# 11_RS232_2.net
KiCad netlist of a schematic drawn in Altium Designer
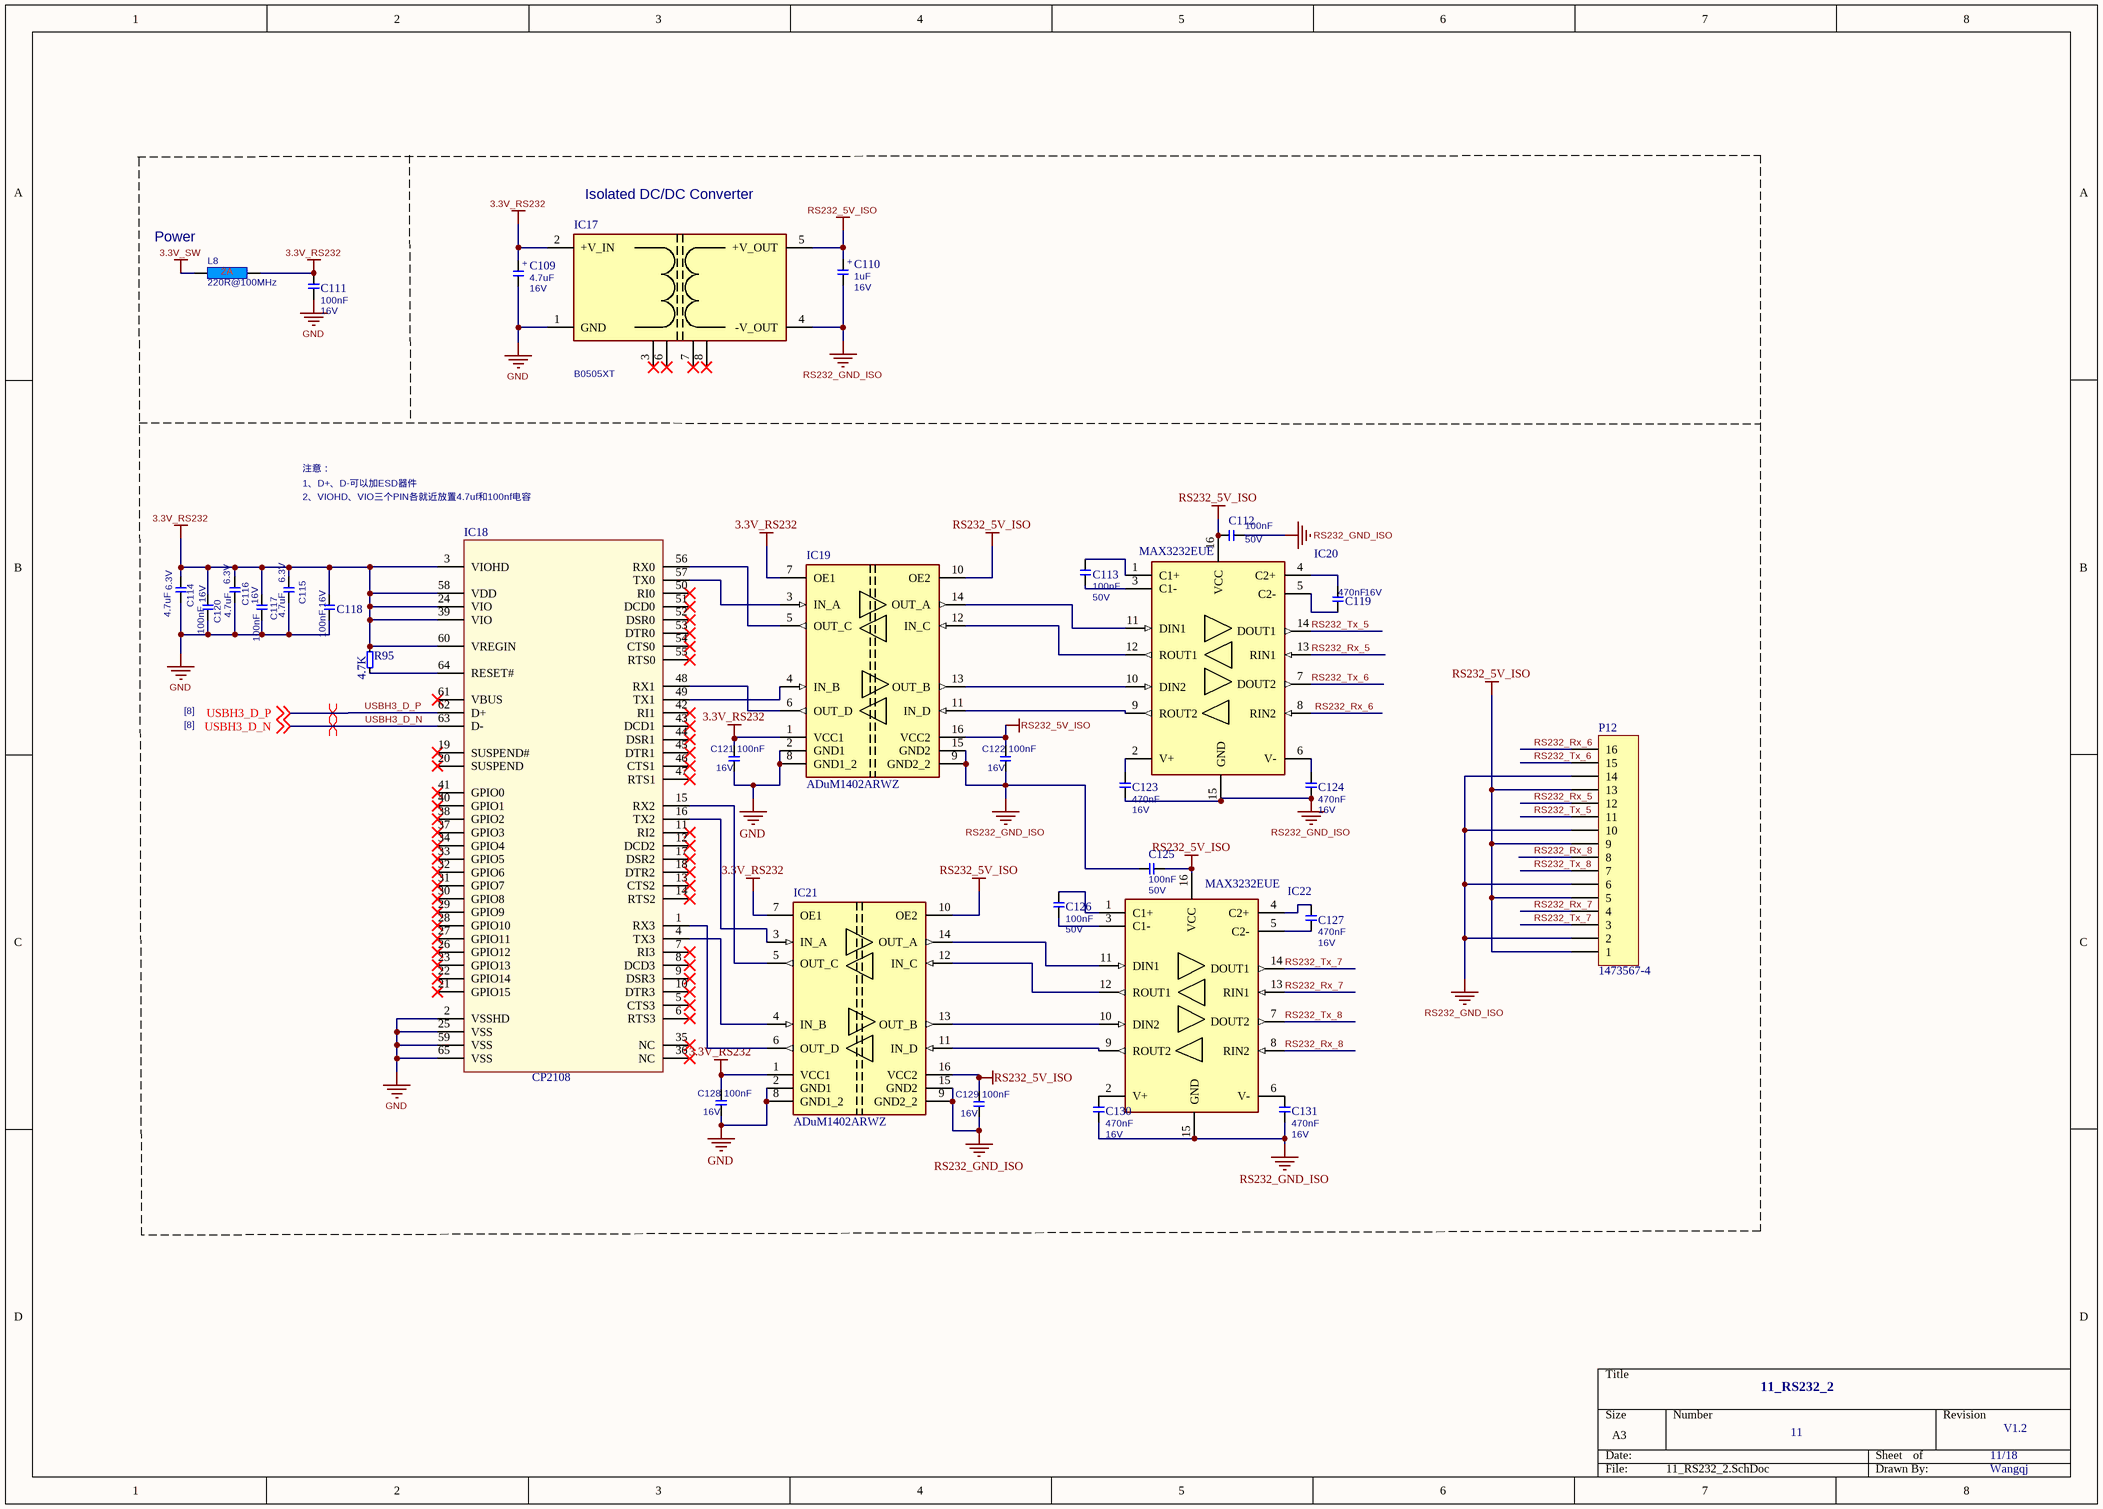
[diagram p0: 11_RS232_2.SchDoc]

(export (version "E")
  (design (tool "Eeschema 10.0.6"))
  (components
    (comp (ref "C109")
      (value "4.7uF")
      (footprint "T_CAPMP3216X180N")
      (description "Capacitor TA 4.7uF 16V 10% 3216")
      (fields (field (name "TOLERANCE") "10%") (field (name "RATING") "16V"))
      (libsource (lib "Apalis Evaluation Board") (part "C-4.7uF-16V-10%-3216-TA"))
    )
    (comp (ref "C110")
      (value "1uF")
      (footprint "T_CAPMP3216X180N")
      (description "Capacitor TA 1uF 16V 10% 3216")
      (fields (field (name "TOLERANCE") "10%") (field (name "RATING") "16V"))
      (libsource (lib "Apalis Evaluation Board") (part "C-1uF-16V-10%-3216-TA"))
    )
    (comp (ref "C111")
      (value "100nF")
      (footprint "T_CAPC0603X33N")
      (description "Capacitor Ceramic X7R 100nF 16V 10% 0603")
      (fields (field (name "TOLERANCE") "10%") (field (name "RATING") "16V"))
      (libsource (lib "Apalis Evaluation Board") (part "C-100nF-16V-10%-0603-X7R"))
    )
    (comp (ref "C112")
      (value "100nF")
      (footprint "T_CAPC0603X33N")
      (description "Capacitor Ceramic X7R 100nF 50V 20% 0603")
      (fields (field (name "TOLERANCE") "20%") (field (name "RATING") "50V"))
      (libsource (lib "Apalis Evaluation Board") (part "C-X7R-100nF-50V-20%-0603"))
    )
    (comp (ref "C113")
      (value "100nF")
      (footprint "T_CAPC0603X33N")
      (description "Capacitor Ceramic X7R 100nF 50V 20% 0603")
      (fields (field (name "TOLERANCE") "20%") (field (name "RATING") "50V"))
      (libsource (lib "Apalis Evaluation Board") (part "C-X7R-100nF-50V-20%-0603"))
    )
    (comp (ref "C114")
      (value "4.7uF")
      (footprint "T_CAPC0603X33N")
      (description "Capacitor Ceramic X5R 4.7uF 6.3V 20% 0603")
      (fields (field (name "TOLERANCE") "20%") (field (name "RATING") "6.3V"))
      (libsource (lib "Apalis Evaluation Board") (part "C-4.7uF-6.3V-20%-0603-X5R"))
    )
    (comp (ref "C115")
      (value "4.7uF")
      (footprint "T_CAPC0603X33N")
      (description "Capacitor Ceramic X5R 4.7uF 6.3V 20% 0603")
      (fields (field (name "TOLERANCE") "20%") (field (name "RATING") "6.3V"))
      (libsource (lib "Apalis Evaluation Board") (part "C-4.7uF-6.3V-20%-0603-X5R"))
    )
    (comp (ref "C116")
      (value "4.7uF")
      (footprint "T_CAPC0603X33N")
      (description "Capacitor Ceramic X5R 4.7uF 6.3V 20% 0603")
      (fields (field (name "TOLERANCE") "20%") (field (name "RATING") "6.3V"))
      (libsource (lib "Apalis Evaluation Board") (part "C-4.7uF-6.3V-20%-0603-X5R"))
    )
    (comp (ref "C117")
      (value "100nF")
      (footprint "T_CAPC0603X33N")
      (description "Capacitor Ceramic X7R 100nF 16V 10% 0603")
      (fields (field (name "TOLERANCE") "10%") (field (name "RATING") "16V"))
      (libsource (lib "Apalis Evaluation Board") (part "C-100nF-16V-10%-0603-X7R"))
    )
    (comp (ref "C118")
      (value "100nF")
      (footprint "T_CAPC0603X33N")
      (description "Capacitor Ceramic X7R 100nF 16V 10% 0603")
      (fields (field (name "TOLERANCE") "10%") (field (name "RATING") "16V"))
      (libsource (lib "Apalis Evaluation Board") (part "C-100nF-16V-10%-0603-X7R"))
    )
    (comp (ref "C119")
      (value "470nF")
      (footprint "T_CAPC0603X33N")
      (description "Capacitor Ceramic X7R 470nF 16V 10% 0603")
      (fields (field (name "TOLERANCE") "10%") (field (name "RATING") "16V"))
      (libsource (lib "Apalis Evaluation Board") (part "C-X7R-470nF-16V-10%-0603"))
    )
    (comp (ref "C120")
      (value "100nF")
      (footprint "T_CAPC0603X33N")
      (description "Capacitor Ceramic X7R 100nF 16V 10% 0603")
      (fields (field (name "TOLERANCE") "10%") (field (name "RATING") "16V"))
      (libsource (lib "Apalis Evaluation Board") (part "C-100nF-16V-10%-0603-X7R"))
    )
    (comp (ref "C121")
      (value "100nF")
      (footprint "T_CAPC0603X33N")
      (description "Capacitor Ceramic X7R 100nF 16V 10% 0603")
      (fields (field (name "TOLERANCE") "10%") (field (name "RATING") "16V"))
      (libsource (lib "Apalis Evaluation Board") (part "C-X7R-100nF-16V-10%-0603"))
    )
    (comp (ref "C122")
      (value "100nF")
      (footprint "T_CAPC0603X33N")
      (description "Capacitor Ceramic X7R 100nF 16V 10% 0603")
      (fields (field (name "TOLERANCE") "10%") (field (name "RATING") "16V"))
      (libsource (lib "Apalis Evaluation Board") (part "C-X7R-100nF-16V-10%-0603"))
    )
    (comp (ref "C123")
      (value "470nF")
      (footprint "T_CAPC0603X33N")
      (description "Capacitor Ceramic X7R 470nF 16V 10% 0603")
      (fields (field (name "TOLERANCE") "10%") (field (name "RATING") "16V"))
      (libsource (lib "Apalis Evaluation Board") (part "C-X7R-470nF-16V-10%-0603"))
    )
    (comp (ref "C124")
      (value "470nF")
      (footprint "T_CAPC0603X33N")
      (description "Capacitor Ceramic X7R 470nF 16V 10% 0603")
      (fields (field (name "TOLERANCE") "10%") (field (name "RATING") "16V"))
      (libsource (lib "Apalis Evaluation Board") (part "C-X7R-470nF-16V-10%-0603"))
    )
    (comp (ref "C125")
      (value "100nF")
      (footprint "T_CAPC0603X33N")
      (description "Capacitor Ceramic X7R 100nF 50V 20% 0603")
      (fields (field (name "TOLERANCE") "20%") (field (name "RATING") "50V"))
      (libsource (lib "Apalis Evaluation Board") (part "C-X7R-100nF-50V-20%-0603"))
    )
    (comp (ref "C126")
      (value "100nF")
      (footprint "T_CAPC0603X33N")
      (description "Capacitor Ceramic X7R 100nF 50V 20% 0603")
      (fields (field (name "TOLERANCE") "20%") (field (name "RATING") "50V"))
      (libsource (lib "Apalis Evaluation Board") (part "C-X7R-100nF-50V-20%-0603"))
    )
    (comp (ref "C127")
      (value "470nF")
      (footprint "T_CAPC0603X33N")
      (description "Capacitor Ceramic X7R 470nF 16V 10% 0603")
      (fields (field (name "TOLERANCE") "10%") (field (name "RATING") "16V"))
      (libsource (lib "Apalis Evaluation Board") (part "C-X7R-470nF-16V-10%-0603"))
    )
    (comp (ref "C128")
      (value "100nF")
      (footprint "T_CAPC0603X33N")
      (description "Capacitor Ceramic X7R 100nF 16V 10% 0603")
      (fields (field (name "TOLERANCE") "10%") (field (name "RATING") "16V"))
      (libsource (lib "Apalis Evaluation Board") (part "C-X7R-100nF-16V-10%-0603"))
    )
    (comp (ref "C129")
      (value "100nF")
      (footprint "T_CAPC0603X33N")
      (description "Capacitor Ceramic X7R 100nF 16V 10% 0603")
      (fields (field (name "TOLERANCE") "10%") (field (name "RATING") "16V"))
      (libsource (lib "Apalis Evaluation Board") (part "C-X7R-100nF-16V-10%-0603"))
    )
    (comp (ref "C130")
      (value "470nF")
      (footprint "T_CAPC0603X33N")
      (description "Capacitor Ceramic X7R 470nF 16V 10% 0603")
      (fields (field (name "TOLERANCE") "10%") (field (name "RATING") "16V"))
      (libsource (lib "Apalis Evaluation Board") (part "C-X7R-470nF-16V-10%-0603"))
    )
    (comp (ref "C131")
      (value "470nF")
      (footprint "T_CAPC0603X33N")
      (description "Capacitor Ceramic X7R 470nF 16V 10% 0603")
      (fields (field (name "TOLERANCE") "10%") (field (name "RATING") "16V"))
      (libsource (lib "Apalis Evaluation Board") (part "C-X7R-470nF-16V-10%-0603"))
    )
    (comp (ref "IC17")
      (value "B0505XT-1W")
      (footprint "MORNSUN_B0305XT-1W_SMD")
      (description "MORNSUN Isolated DC/DC Converter")
      (fields (field (name "MANUFACTURER PART NO.") "B0505XT"))
      (libsource (lib "Apalis Evaluation Board") (part "IC-MORNSUN-B0505XT-SMD"))
    )
    (comp (ref "IC18")
      (value "CP2108")
      (footprint "QFN50P900X900X90_HS-65N")
      (description "Single-Chip USB To Quad UART Bridge")
      (fields (field (name "MANUCFACTURER PART NO.") "CP2108"))
      (libsource (lib "Apalis Evaluation Board") (part "IC-SILICON-CP2108"))
    )
    (comp (ref "IC19")
      (value "ADuM1402ARWZ")
      (footprint "T_AD_ADuM1300ARW")
      (description "Digital Isolator")
      (libsource (lib "Apalis Evaluation Board") (part "IC-AD-ADuM1402ARWZ"))
    )
    (comp (ref "IC20")
      (value "MAX3232EUE")
      (footprint "LC-TSSOP-16")
      (description "RS232")
      (libsource (lib "Apalis Evaluation Board") (part "IC-MAXIM-MAX3232"))
    )
    (comp (ref "IC21")
      (value "ADuM1402ARWZ")
      (footprint "T_AD_ADuM1300ARW")
      (description "Digital Isolator")
      (libsource (lib "Apalis Evaluation Board") (part "IC-AD-ADuM1402ARWZ"))
    )
    (comp (ref "IC22")
      (value "MAX3232EUE")
      (footprint "LC-TSSOP-16")
      (description "RS232")
      (libsource (lib "Apalis Evaluation Board") (part "IC-MAXIM-MAX3232"))
    )
    (comp (ref "L8")
      (value "220R@100MHz")
      (footprint "INDC1608X95N")
      (description "220R@100MHz 2A EMI FILTER")
      (fields (field (name "TOLERANCE") "25%"))
      (libsource (lib "Apalis Evaluation Board") (part "L-220R@100MHz-2A-25%-0603"))
    )
    (comp (ref "P12")
      (value "1473567-4")
      (footprint "147-4")
      (description "泰科4P端子")
      (fields (field (name "PUBLISHER") "Altium Limited"))
      (libsource (lib "Miscellaneous Connectors") (part "MHDR1X16"))
    )
    (comp (ref "R95")
      (value "4.7K")
      (footprint "t_RESC0603X30N")
      (description "Resistor 4.7 Kohm 63mW 5% 0603")
      (fields (field (name "TOLERANCE") "5%"))
      (libsource (lib "Apalis Evaluation Board") (part "R-4.7kR-63mW-5%-0603"))
    )
  )
  (nets
    (net (code "1") (name "/RS232_Rx_5") (class "Default")
      (node (ref "IC20") (pin "13") (pinfunction "RIN1_13") (pintype "input"))
      (node (ref "P12") (pin "12") (pinfunction "12_12") (pintype "passive"))
    )
    (net (code "2") (name "/RS232_Rx_6") (class "Default")
      (node (ref "IC20") (pin "8") (pinfunction "RIN2_8") (pintype "input"))
      (node (ref "P12") (pin "16") (pinfunction "16_16") (pintype "passive"))
    )
    (net (code "3") (name "/RS232_Rx_7") (class "Default")
      (node (ref "IC22") (pin "13") (pinfunction "RIN1_13") (pintype "input"))
      (node (ref "P12") (pin "4") (pinfunction "4_4") (pintype "passive"))
    )
    (net (code "4") (name "/RS232_Rx_8") (class "Default")
      (node (ref "IC22") (pin "8") (pinfunction "RIN2_8") (pintype "input"))
      (node (ref "P12") (pin "8") (pinfunction "8_8") (pintype "passive"))
    )
    (net (code "5") (name "/RS232_Tx_5") (class "Default")
      (node (ref "IC20") (pin "14") (pinfunction "DOUT1_14") (pintype "output"))
      (node (ref "P12") (pin "11") (pinfunction "11_11") (pintype "passive"))
    )
    (net (code "6") (name "/RS232_Tx_6") (class "Default")
      (node (ref "IC20") (pin "7") (pinfunction "DOUT2_7") (pintype "output"))
      (node (ref "P12") (pin "15") (pinfunction "15_15") (pintype "passive"))
    )
    (net (code "7") (name "/RS232_Tx_7") (class "Default")
      (node (ref "IC22") (pin "14") (pinfunction "DOUT1_14") (pintype "output"))
      (node (ref "P12") (pin "3") (pinfunction "3_3") (pintype "passive"))
    )
    (net (code "8") (name "/RS232_Tx_8") (class "Default")
      (node (ref "IC22") (pin "7") (pinfunction "DOUT2_7") (pintype "output"))
      (node (ref "P12") (pin "7") (pinfunction "7_7") (pintype "passive"))
    )
    (net (code "9") (name "3.3V_RS232") (class "Default")
      (node (ref "C109") (pin "1") (pinfunction "1_1") (pintype "passive"))
      (node (ref "C111") (pin "2") (pinfunction "2_2") (pintype "passive"))
      (node (ref "C114") (pin "2") (pinfunction "2_2") (pintype "passive"))
      (node (ref "C115") (pin "2") (pinfunction "2_2") (pintype "passive"))
      (node (ref "C116") (pin "2") (pinfunction "2_2") (pintype "passive"))
      (node (ref "C117") (pin "2") (pinfunction "2_2") (pintype "passive"))
      (node (ref "C118") (pin "2") (pinfunction "2_2") (pintype "passive"))
      (node (ref "C120") (pin "2") (pinfunction "2_2") (pintype "passive"))
      (node (ref "C121") (pin "2") (pinfunction "2_2") (pintype "passive"))
      (node (ref "C128") (pin "2") (pinfunction "2_2") (pintype "passive"))
      (node (ref "IC17") (pin "2") (pinfunction "+V_IN_2") (pintype "power_in"))
      (node (ref "IC18") (pin "24") (pinfunction "VIO_24") (pintype "power_in"))
      (node (ref "IC18") (pin "3") (pinfunction "VIOHD_3") (pintype "power_in"))
      (node (ref "IC18") (pin "39") (pinfunction "VIO_39") (pintype "passive"))
      (node (ref "IC18") (pin "58") (pinfunction "VDD_58") (pintype "passive"))
      (node (ref "IC18") (pin "60") (pinfunction "VREGIN_60") (pintype "passive"))
      (node (ref "IC19") (pin "1") (pinfunction "VCC1_1") (pintype "passive"))
      (node (ref "IC19") (pin "7") (pinfunction "OE1_7") (pintype "passive"))
      (node (ref "IC21") (pin "1") (pinfunction "VCC1_1") (pintype "passive"))
      (node (ref "IC21") (pin "7") (pinfunction "OE1_7") (pintype "passive"))
      (node (ref "L8") (pin "2") (pinfunction "2_2") (pintype "passive"))
      (node (ref "R95") (pin "2") (pinfunction "2_2") (pintype "passive"))
    )
    (net (code "10") (name "3.3V_SW") (class "Default")
      (node (ref "L8") (pin "1") (pinfunction "1_1") (pintype "passive"))
    )
    (net (code "11") (name "GND") (class "Default")
      (node (ref "C109") (pin "2") (pinfunction "2_2") (pintype "passive"))
      (node (ref "C111") (pin "1") (pinfunction "1_1") (pintype "passive"))
      (node (ref "C114") (pin "1") (pinfunction "1_1") (pintype "passive"))
      (node (ref "C115") (pin "1") (pinfunction "1_1") (pintype "passive"))
      (node (ref "C116") (pin "1") (pinfunction "1_1") (pintype "passive"))
      (node (ref "C117") (pin "1") (pinfunction "1_1") (pintype "passive"))
      (node (ref "C118") (pin "1") (pinfunction "1_1") (pintype "passive"))
      (node (ref "C120") (pin "1") (pinfunction "1_1") (pintype "passive"))
      (node (ref "C121") (pin "1") (pinfunction "1_1") (pintype "passive"))
      (node (ref "C128") (pin "1") (pinfunction "1_1") (pintype "passive"))
      (node (ref "IC17") (pin "1") (pinfunction "GND_1") (pintype "power_in"))
      (node (ref "IC18") (pin "2") (pinfunction "VSSHD_2") (pintype "passive"))
      (node (ref "IC18") (pin "25") (pinfunction "VSS_25") (pintype "power_in"))
      (node (ref "IC18") (pin "59") (pinfunction "VSS_59") (pintype "passive"))
      (node (ref "IC18") (pin "65") (pinfunction "VSS_65") (pintype "passive"))
      (node (ref "IC19") (pin "2") (pinfunction "GND1_2") (pintype "power_in"))
      (node (ref "IC19") (pin "8") (pinfunction "GND1_2_8") (pintype "power_in"))
      (node (ref "IC21") (pin "2") (pinfunction "GND1_2") (pintype "power_in"))
      (node (ref "IC21") (pin "8") (pinfunction "GND1_2_8") (pintype "power_in"))
    )
    (net (code "12") (name "Net-(IC18-RESET#)") (class "Default")
      (node (ref "IC18") (pin "64") (pinfunction "RESET#_64") (pintype "passive"))
      (node (ref "R95") (pin "1") (pinfunction "1_1") (pintype "passive"))
    )
    (net (code "13") (name "Net-(IC18-RX0)") (class "Default")
      (node (ref "IC18") (pin "56") (pinfunction "RX0_56") (pintype "passive"))
      (node (ref "IC19") (pin "5") (pinfunction "OUT_C_5") (pintype "output"))
    )
    (net (code "14") (name "Net-(IC18-RX1)") (class "Default")
      (node (ref "IC18") (pin "48") (pinfunction "RX1_48") (pintype "passive"))
      (node (ref "IC19") (pin "6") (pinfunction "OUT_D_6") (pintype "output"))
    )
    (net (code "15") (name "Net-(IC18-RX2)") (class "Default")
      (node (ref "IC18") (pin "15") (pinfunction "RX2_15") (pintype "passive"))
      (node (ref "IC21") (pin "5") (pinfunction "OUT_C_5") (pintype "output"))
    )
    (net (code "16") (name "Net-(IC18-RX3)") (class "Default")
      (node (ref "IC18") (pin "1") (pinfunction "RX3_1") (pintype "passive"))
      (node (ref "IC21") (pin "6") (pinfunction "OUT_D_6") (pintype "output"))
    )
    (net (code "17") (name "Net-(IC18-TX0)") (class "Default")
      (node (ref "IC18") (pin "57") (pinfunction "TX0_57") (pintype "passive"))
      (node (ref "IC19") (pin "3") (pinfunction "IN_A_3") (pintype "input"))
    )
    (net (code "18") (name "Net-(IC18-TX1)") (class "Default")
      (node (ref "IC18") (pin "49") (pinfunction "TX1_49") (pintype "passive"))
      (node (ref "IC19") (pin "4") (pinfunction "IN_B_4") (pintype "input"))
    )
    (net (code "19") (name "Net-(IC18-TX2)") (class "Default")
      (node (ref "IC18") (pin "16") (pinfunction "TX2_16") (pintype "passive"))
      (node (ref "IC21") (pin "3") (pinfunction "IN_A_3") (pintype "input"))
    )
    (net (code "20") (name "Net-(IC18-TX3)") (class "Default")
      (node (ref "IC18") (pin "4") (pinfunction "TX3_4") (pintype "passive"))
      (node (ref "IC21") (pin "4") (pinfunction "IN_B_4") (pintype "input"))
    )
    (net (code "21") (name "Net-(IC19-IN_C)") (class "Default")
      (node (ref "IC19") (pin "12") (pinfunction "IN_C_12") (pintype "input"))
      (node (ref "IC20") (pin "12") (pinfunction "ROUT1_12") (pintype "output"))
    )
    (net (code "22") (name "Net-(IC19-IN_D)") (class "Default")
      (node (ref "IC19") (pin "11") (pinfunction "IN_D_11") (pintype "input"))
      (node (ref "IC20") (pin "9") (pinfunction "ROUT2_9") (pintype "output"))
    )
    (net (code "23") (name "Net-(IC19-OUT_A)") (class "Default")
      (node (ref "IC19") (pin "14") (pinfunction "OUT_A_14") (pintype "output"))
      (node (ref "IC20") (pin "11") (pinfunction "DIN1_11") (pintype "input"))
    )
    (net (code "24") (name "Net-(IC19-OUT_B)") (class "Default")
      (node (ref "IC19") (pin "13") (pinfunction "OUT_B_13") (pintype "output"))
      (node (ref "IC20") (pin "10") (pinfunction "DIN2_10") (pintype "input"))
    )
    (net (code "25") (name "Net-(IC20-C1+)") (class "Default")
      (node (ref "C113") (pin "2") (pinfunction "2_2") (pintype "passive"))
      (node (ref "IC20") (pin "1") (pinfunction "C1+_1") (pintype "passive"))
    )
    (net (code "26") (name "Net-(IC20-C1-)") (class "Default")
      (node (ref "C113") (pin "1") (pinfunction "1_1") (pintype "passive"))
      (node (ref "IC20") (pin "3") (pinfunction "C1-_3") (pintype "power_in"))
    )
    (net (code "27") (name "Net-(IC20-C2+)") (class "Default")
      (node (ref "C119") (pin "2") (pinfunction "2_2") (pintype "passive"))
      (node (ref "IC20") (pin "4") (pinfunction "C2+_4") (pintype "passive"))
    )
    (net (code "28") (name "Net-(IC20-C2-)") (class "Default")
      (node (ref "C119") (pin "1") (pinfunction "1_1") (pintype "passive"))
      (node (ref "IC20") (pin "5") (pinfunction "C2-_5") (pintype "power_in"))
    )
    (net (code "29") (name "Net-(IC20-V+)") (class "Default")
      (node (ref "C123") (pin "2") (pinfunction "2_2") (pintype "passive"))
      (node (ref "IC20") (pin "2") (pinfunction "V+_2") (pintype "passive"))
    )
    (net (code "30") (name "Net-(IC20-V-)") (class "Default")
      (node (ref "C124") (pin "2") (pinfunction "2_2") (pintype "passive"))
      (node (ref "IC20") (pin "6") (pinfunction "V-_6") (pintype "passive"))
    )
    (net (code "31") (name "Net-(IC21-IN_C)") (class "Default")
      (node (ref "IC21") (pin "12") (pinfunction "IN_C_12") (pintype "input"))
      (node (ref "IC22") (pin "12") (pinfunction "ROUT1_12") (pintype "output"))
    )
    (net (code "32") (name "Net-(IC21-IN_D)") (class "Default")
      (node (ref "IC21") (pin "11") (pinfunction "IN_D_11") (pintype "input"))
      (node (ref "IC22") (pin "9") (pinfunction "ROUT2_9") (pintype "output"))
    )
    (net (code "33") (name "Net-(IC21-OUT_A)") (class "Default")
      (node (ref "IC21") (pin "14") (pinfunction "OUT_A_14") (pintype "output"))
      (node (ref "IC22") (pin "11") (pinfunction "DIN1_11") (pintype "input"))
    )
    (net (code "34") (name "Net-(IC21-OUT_B)") (class "Default")
      (node (ref "IC21") (pin "13") (pinfunction "OUT_B_13") (pintype "output"))
      (node (ref "IC22") (pin "10") (pinfunction "DIN2_10") (pintype "input"))
    )
    (net (code "35") (name "Net-(IC22-C1+)") (class "Default")
      (node (ref "C126") (pin "2") (pinfunction "2_2") (pintype "passive"))
      (node (ref "IC22") (pin "1") (pinfunction "C1+_1") (pintype "passive"))
    )
    (net (code "36") (name "Net-(IC22-C1-)") (class "Default")
      (node (ref "C126") (pin "1") (pinfunction "1_1") (pintype "passive"))
      (node (ref "IC22") (pin "3") (pinfunction "C1-_3") (pintype "power_in"))
    )
    (net (code "37") (name "Net-(IC22-C2+)") (class "Default")
      (node (ref "C127") (pin "2") (pinfunction "2_2") (pintype "passive"))
      (node (ref "IC22") (pin "4") (pinfunction "C2+_4") (pintype "passive"))
    )
    (net (code "38") (name "Net-(IC22-C2-)") (class "Default")
      (node (ref "C127") (pin "1") (pinfunction "1_1") (pintype "passive"))
      (node (ref "IC22") (pin "5") (pinfunction "C2-_5") (pintype "power_in"))
    )
    (net (code "39") (name "Net-(IC22-V+)") (class "Default")
      (node (ref "C130") (pin "2") (pinfunction "2_2") (pintype "passive"))
      (node (ref "IC22") (pin "2") (pinfunction "V+_2") (pintype "passive"))
    )
    (net (code "40") (name "Net-(IC22-V-)") (class "Default")
      (node (ref "C131") (pin "2") (pinfunction "2_2") (pintype "passive"))
      (node (ref "IC22") (pin "6") (pinfunction "V-_6") (pintype "passive"))
    )
    (net (code "41") (name "RS232_5V_ISO") (class "Default")
      (node (ref "C110") (pin "1") (pinfunction "1_1") (pintype "passive"))
      (node (ref "C112") (pin "2") (pinfunction "2_2") (pintype "passive"))
      (node (ref "C122") (pin "2") (pinfunction "2_2") (pintype "passive"))
      (node (ref "C125") (pin "1") (pinfunction "1_1") (pintype "passive"))
      (node (ref "C129") (pin "2") (pinfunction "2_2") (pintype "passive"))
      (node (ref "IC17") (pin "5") (pinfunction "+V_OUT_5") (pintype "power_in"))
      (node (ref "IC19") (pin "10") (pinfunction "OE2_10") (pintype "passive"))
      (node (ref "IC19") (pin "16") (pinfunction "VCC2_16") (pintype "passive"))
      (node (ref "IC20") (pin "16") (pinfunction "VCC_16") (pintype "power_in"))
      (node (ref "IC21") (pin "10") (pinfunction "OE2_10") (pintype "passive"))
      (node (ref "IC21") (pin "16") (pinfunction "VCC2_16") (pintype "passive"))
      (node (ref "IC22") (pin "16") (pinfunction "VCC_16") (pintype "power_in"))
      (node (ref "P12") (pin "1") (pinfunction "1_1") (pintype "passive"))
      (node (ref "P12") (pin "13") (pinfunction "13_13") (pintype "passive"))
      (node (ref "P12") (pin "5") (pinfunction "5_5") (pintype "passive"))
      (node (ref "P12") (pin "9") (pinfunction "9_9") (pintype "passive"))
    )
    (net (code "42") (name "RS232_GND_ISO") (class "Default")
      (node (ref "C110") (pin "2") (pinfunction "2_2") (pintype "passive"))
      (node (ref "C112") (pin "1") (pinfunction "1_1") (pintype "passive"))
      (node (ref "C122") (pin "1") (pinfunction "1_1") (pintype "passive"))
      (node (ref "C123") (pin "1") (pinfunction "1_1") (pintype "passive"))
      (node (ref "C124") (pin "1") (pinfunction "1_1") (pintype "passive"))
      (node (ref "C125") (pin "2") (pinfunction "2_2") (pintype "passive"))
      (node (ref "C129") (pin "1") (pinfunction "1_1") (pintype "passive"))
      (node (ref "C130") (pin "1") (pinfunction "1_1") (pintype "passive"))
      (node (ref "C131") (pin "1") (pinfunction "1_1") (pintype "passive"))
      (node (ref "IC17") (pin "4") (pinfunction "-V_OUT_4") (pintype "power_in"))
      (node (ref "IC19") (pin "15") (pinfunction "GND2_15") (pintype "power_in"))
      (node (ref "IC19") (pin "9") (pinfunction "GND2_2_9") (pintype "power_in"))
      (node (ref "IC20") (pin "15") (pinfunction "GND_15") (pintype "power_in"))
      (node (ref "IC21") (pin "15") (pinfunction "GND2_15") (pintype "power_in"))
      (node (ref "IC21") (pin "9") (pinfunction "GND2_2_9") (pintype "power_in"))
      (node (ref "IC22") (pin "15") (pinfunction "GND_15") (pintype "power_in"))
      (node (ref "P12") (pin "10") (pinfunction "10_10") (pintype "passive"))
      (node (ref "P12") (pin "14") (pinfunction "14_14") (pintype "passive"))
      (node (ref "P12") (pin "2") (pinfunction "2_2") (pintype "passive"))
      (node (ref "P12") (pin "6") (pinfunction "6_6") (pintype "passive"))
    )
    (net (code "43") (name "USBH3_D_N") (class "Default")
      (node (ref "IC18") (pin "63") (pinfunction "D-_63") (pintype "passive"))
    )
    (net (code "44") (name "USBH3_D_P") (class "Default")
      (node (ref "IC18") (pin "62") (pinfunction "D+_62") (pintype "passive"))
    )
    (net (code "45") (name "unconnected-(IC17-NC-Pad3)") (class "Default")
      (node (ref "IC17") (pin "3") (pinfunction "NC_3") (pintype "passive+no_connect"))
    )
    (net (code "46") (name "unconnected-(IC17-NC-Pad6)") (class "Default")
      (node (ref "IC17") (pin "6") (pinfunction "NC_6") (pintype "passive+no_connect"))
    )
    (net (code "47") (name "unconnected-(IC17-NC-Pad7)") (class "Default")
      (node (ref "IC17") (pin "7") (pinfunction "NC_7") (pintype "passive+no_connect"))
    )
    (net (code "48") (name "unconnected-(IC17-NC-Pad8)") (class "Default")
      (node (ref "IC17") (pin "8") (pinfunction "NC_8") (pintype "passive+no_connect"))
    )
    (net (code "49") (name "unconnected-(IC18-CTS0-Pad54)") (class "Default")
      (node (ref "IC18") (pin "54") (pinfunction "CTS0_54") (pintype "passive+no_connect"))
    )
    (net (code "50") (name "unconnected-(IC18-CTS1-Pad46)") (class "Default")
      (node (ref "IC18") (pin "46") (pinfunction "CTS1_46") (pintype "passive+no_connect"))
    )
    (net (code "51") (name "unconnected-(IC18-CTS2-Pad13)") (class "Default")
      (node (ref "IC18") (pin "13") (pinfunction "CTS2_13") (pintype "passive+no_connect"))
    )
    (net (code "52") (name "unconnected-(IC18-CTS3-Pad5)") (class "Default")
      (node (ref "IC18") (pin "5") (pinfunction "CTS3_5") (pintype "passive+no_connect"))
    )
    (net (code "53") (name "unconnected-(IC18-DCD0-Pad51)") (class "Default")
      (node (ref "IC18") (pin "51") (pinfunction "DCD0_51") (pintype "passive+no_connect"))
    )
    (net (code "54") (name "unconnected-(IC18-DCD1-Pad43)") (class "Default")
      (node (ref "IC18") (pin "43") (pinfunction "DCD1_43") (pintype "passive+no_connect"))
    )
    (net (code "55") (name "unconnected-(IC18-DCD2-Pad12)") (class "Default")
      (node (ref "IC18") (pin "12") (pinfunction "DCD2_12") (pintype "passive+no_connect"))
    )
    (net (code "56") (name "unconnected-(IC18-DCD3-Pad8)") (class "Default")
      (node (ref "IC18") (pin "8") (pinfunction "DCD3_8") (pintype "passive+no_connect"))
    )
    (net (code "57") (name "unconnected-(IC18-DSR0-Pad52)") (class "Default")
      (node (ref "IC18") (pin "52") (pinfunction "DSR0_52") (pintype "passive+no_connect"))
    )
    (net (code "58") (name "unconnected-(IC18-DSR1-Pad44)") (class "Default")
      (node (ref "IC18") (pin "44") (pinfunction "DSR1_44") (pintype "passive+no_connect"))
    )
    (net (code "59") (name "unconnected-(IC18-DSR2-Pad17)") (class "Default")
      (node (ref "IC18") (pin "17") (pinfunction "DSR2_17") (pintype "passive+no_connect"))
    )
    (net (code "60") (name "unconnected-(IC18-DSR3-Pad9)") (class "Default")
      (node (ref "IC18") (pin "9") (pinfunction "DSR3_9") (pintype "passive+no_connect"))
    )
    (net (code "61") (name "unconnected-(IC18-DTR0-Pad53)") (class "Default")
      (node (ref "IC18") (pin "53") (pinfunction "DTR0_53") (pintype "passive+no_connect"))
    )
    (net (code "62") (name "unconnected-(IC18-DTR1-Pad45)") (class "Default")
      (node (ref "IC18") (pin "45") (pinfunction "DTR1_45") (pintype "passive+no_connect"))
    )
    (net (code "63") (name "unconnected-(IC18-DTR2-Pad18)") (class "Default")
      (node (ref "IC18") (pin "18") (pinfunction "DTR2_18") (pintype "passive+no_connect"))
    )
    (net (code "64") (name "unconnected-(IC18-DTR3-Pad10)") (class "Default")
      (node (ref "IC18") (pin "10") (pinfunction "DTR3_10") (pintype "passive+no_connect"))
    )
    (net (code "65") (name "unconnected-(IC18-GPIO0-Pad41)") (class "Default")
      (node (ref "IC18") (pin "41") (pinfunction "GPIO0_41") (pintype "passive+no_connect"))
    )
    (net (code "66") (name "unconnected-(IC18-GPIO1-Pad40)") (class "Default")
      (node (ref "IC18") (pin "40") (pinfunction "GPIO1_40") (pintype "passive+no_connect"))
    )
    (net (code "67") (name "unconnected-(IC18-GPIO2-Pad38)") (class "Default")
      (node (ref "IC18") (pin "38") (pinfunction "GPIO2_38") (pintype "passive+no_connect"))
    )
    (net (code "68") (name "unconnected-(IC18-GPIO3-Pad37)") (class "Default")
      (node (ref "IC18") (pin "37") (pinfunction "GPIO3_37") (pintype "passive+no_connect"))
    )
    (net (code "69") (name "unconnected-(IC18-GPIO4-Pad34)") (class "Default")
      (node (ref "IC18") (pin "34") (pinfunction "GPIO4_34") (pintype "passive+no_connect"))
    )
    (net (code "70") (name "unconnected-(IC18-GPIO5-Pad33)") (class "Default")
      (node (ref "IC18") (pin "33") (pinfunction "GPIO5_33") (pintype "passive+no_connect"))
    )
    (net (code "71") (name "unconnected-(IC18-GPIO6-Pad32)") (class "Default")
      (node (ref "IC18") (pin "32") (pinfunction "GPIO6_32") (pintype "passive+no_connect"))
    )
    (net (code "72") (name "unconnected-(IC18-GPIO7-Pad31)") (class "Default")
      (node (ref "IC18") (pin "31") (pinfunction "GPIO7_31") (pintype "passive+no_connect"))
    )
    (net (code "73") (name "unconnected-(IC18-GPIO8-Pad30)") (class "Default")
      (node (ref "IC18") (pin "30") (pinfunction "GPIO8_30") (pintype "passive+no_connect"))
    )
    (net (code "74") (name "unconnected-(IC18-GPIO9-Pad29)") (class "Default")
      (node (ref "IC18") (pin "29") (pinfunction "GPIO9_29") (pintype "passive+no_connect"))
    )
    (net (code "75") (name "unconnected-(IC18-GPIO10-Pad28)") (class "Default")
      (node (ref "IC18") (pin "28") (pinfunction "GPIO10_28") (pintype "passive+no_connect"))
    )
    (net (code "76") (name "unconnected-(IC18-GPIO11-Pad27)") (class "Default")
      (node (ref "IC18") (pin "27") (pinfunction "GPIO11_27") (pintype "passive+no_connect"))
    )
    (net (code "77") (name "unconnected-(IC18-GPIO12-Pad26)") (class "Default")
      (node (ref "IC18") (pin "26") (pinfunction "GPIO12_26") (pintype "passive+no_connect"))
    )
    (net (code "78") (name "unconnected-(IC18-GPIO13-Pad23)") (class "Default")
      (node (ref "IC18") (pin "23") (pinfunction "GPIO13_23") (pintype "passive+no_connect"))
    )
    (net (code "79") (name "unconnected-(IC18-GPIO14-Pad22)") (class "Default")
      (node (ref "IC18") (pin "22") (pinfunction "GPIO14_22") (pintype "passive+no_connect"))
    )
    (net (code "80") (name "unconnected-(IC18-GPIO15-Pad21)") (class "Default")
      (node (ref "IC18") (pin "21") (pinfunction "GPIO15_21") (pintype "passive+no_connect"))
    )
    (net (code "81") (name "unconnected-(IC18-NC-Pad35)") (class "Default")
      (node (ref "IC18") (pin "35") (pinfunction "NC_35") (pintype "passive+no_connect"))
    )
    (net (code "82") (name "unconnected-(IC18-NC-Pad36)") (class "Default")
      (node (ref "IC18") (pin "36") (pinfunction "NC_36") (pintype "passive+no_connect"))
    )
    (net (code "83") (name "unconnected-(IC18-RI0-Pad50)") (class "Default")
      (node (ref "IC18") (pin "50") (pinfunction "RI0_50") (pintype "passive+no_connect"))
    )
    (net (code "84") (name "unconnected-(IC18-RI1-Pad42)") (class "Default")
      (node (ref "IC18") (pin "42") (pinfunction "RI1_42") (pintype "passive+no_connect"))
    )
    (net (code "85") (name "unconnected-(IC18-RI2-Pad11)") (class "Default")
      (node (ref "IC18") (pin "11") (pinfunction "RI2_11") (pintype "passive+no_connect"))
    )
    (net (code "86") (name "unconnected-(IC18-RI3-Pad7)") (class "Default")
      (node (ref "IC18") (pin "7") (pinfunction "RI3_7") (pintype "passive+no_connect"))
    )
    (net (code "87") (name "unconnected-(IC18-RTS0-Pad55)") (class "Default")
      (node (ref "IC18") (pin "55") (pinfunction "RTS0_55") (pintype "passive+no_connect"))
    )
    (net (code "88") (name "unconnected-(IC18-RTS1-Pad47)") (class "Default")
      (node (ref "IC18") (pin "47") (pinfunction "RTS1_47") (pintype "passive+no_connect"))
    )
    (net (code "89") (name "unconnected-(IC18-RTS2-Pad14)") (class "Default")
      (node (ref "IC18") (pin "14") (pinfunction "RTS2_14") (pintype "passive+no_connect"))
    )
    (net (code "90") (name "unconnected-(IC18-RTS3-Pad6)") (class "Default")
      (node (ref "IC18") (pin "6") (pinfunction "RTS3_6") (pintype "passive+no_connect"))
    )
    (net (code "91") (name "unconnected-(IC18-SUSPEND#-Pad19)") (class "Default")
      (node (ref "IC18") (pin "19") (pinfunction "SUSPEND#_19") (pintype "passive+no_connect"))
    )
    (net (code "92") (name "unconnected-(IC18-SUSPEND-Pad20)") (class "Default")
      (node (ref "IC18") (pin "20") (pinfunction "SUSPEND_20") (pintype "passive+no_connect"))
    )
    (net (code "93") (name "unconnected-(IC18-VBUS-Pad61)") (class "Default")
      (node (ref "IC18") (pin "61") (pinfunction "VBUS_61") (pintype "passive+no_connect"))
    )
  )
)
